# I2C-Interface.net
KiCad netlist of a schematic drawn in Altium Designer
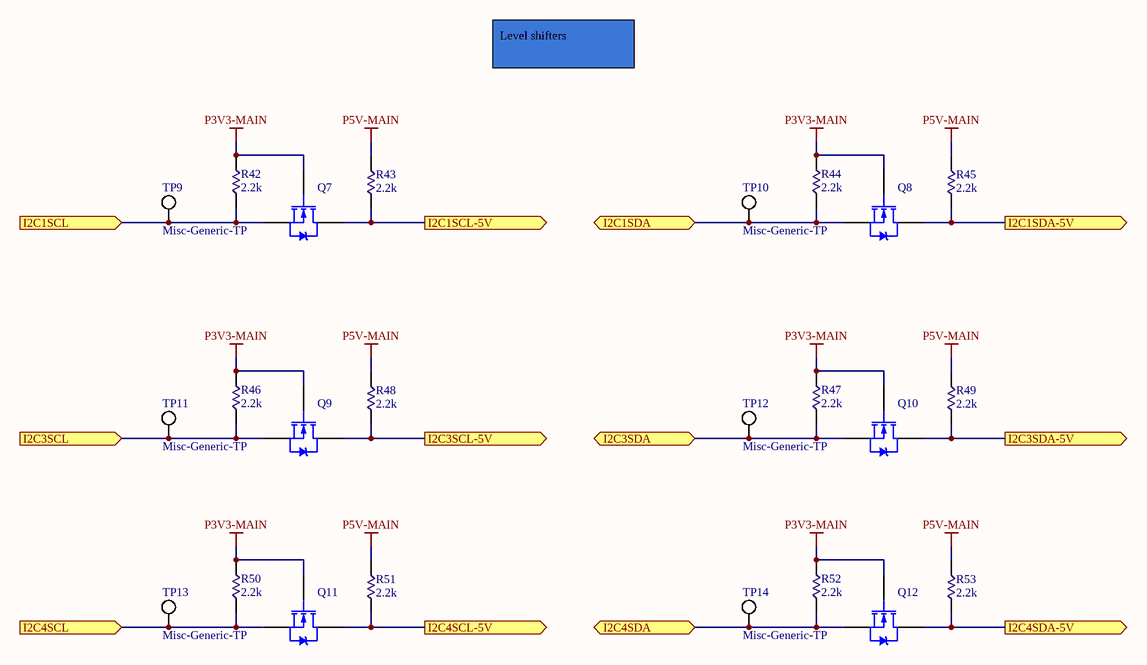
[diagram p0: I2C-Interface.SchDoc]

(export (version "E")
  (design (tool "Eeschema 10.0.6"))
  (components
    (comp (ref "Q7")
      (value "BSS138Q-7-F")
      (footprint "FOOTPRINT-DINC-SOT23-1G2S3D")
      (description "N-Channel Logic Level Enhancement Mode Field Effect Transistor")
      (fields (field (name "PUBLISHER") "Altium Limited"))
      (libsource (lib "HR-Master-Integrated") (part "Transistor-DiodesInc-BSS138-1G2S3D"))
    )
    (comp (ref "Q8")
      (value "BSS138Q-7-F")
      (footprint "FOOTPRINT-DINC-SOT23-1G2S3D")
      (description "N-Channel Logic Level Enhancement Mode Field Effect Transistor")
      (fields (field (name "PUBLISHER") "Altium Limited"))
      (libsource (lib "HR-Master-Integrated") (part "Transistor-DiodesInc-BSS138-1G2S3D"))
    )
    (comp (ref "Q9")
      (value "BSS138Q-7-F")
      (footprint "FOOTPRINT-DINC-SOT23-1G2S3D")
      (description "N-Channel Logic Level Enhancement Mode Field Effect Transistor")
      (fields (field (name "PUBLISHER") "Altium Limited"))
      (libsource (lib "HR-Master-Integrated") (part "Transistor-DiodesInc-BSS138-1G2S3D"))
    )
    (comp (ref "Q10")
      (value "BSS138Q-7-F")
      (footprint "FOOTPRINT-DINC-SOT23-1G2S3D")
      (description "N-Channel Logic Level Enhancement Mode Field Effect Transistor")
      (fields (field (name "PUBLISHER") "Altium Limited"))
      (libsource (lib "HR-Master-Integrated") (part "Transistor-DiodesInc-BSS138-1G2S3D"))
    )
    (comp (ref "Q11")
      (value "BSS138Q-7-F")
      (footprint "FOOTPRINT-DINC-SOT23-1G2S3D")
      (description "N-Channel Logic Level Enhancement Mode Field Effect Transistor")
      (fields (field (name "PUBLISHER") "Altium Limited"))
      (libsource (lib "HR-Master-Integrated") (part "Transistor-DiodesInc-BSS138-1G2S3D"))
    )
    (comp (ref "Q12")
      (value "BSS138Q-7-F")
      (footprint "FOOTPRINT-DINC-SOT23-1G2S3D")
      (description "N-Channel Logic Level Enhancement Mode Field Effect Transistor")
      (fields (field (name "PUBLISHER") "Altium Limited"))
      (libsource (lib "HR-Master-Integrated") (part "Transistor-DiodesInc-BSS138-1G2S3D"))
    )
    (comp (ref "R42")
      (value "2.2k")
      (footprint "FOOTPRINT-0805-GEN")
      (description "1/8 Watt Surface Mount Resistor")
      (fields (field (name "Comment") "SMC"))
      (libsource (lib "HR-Master-Integrated") (part "Resistor-Generic-0805-2012"))
    )
    (comp (ref "R43")
      (value "2.2k")
      (footprint "FOOTPRINT-0805-GEN")
      (description "1/8 Watt Surface Mount Resistor")
      (fields (field (name "Comment") "SMC"))
      (libsource (lib "HR-Master-Integrated") (part "Resistor-Generic-0805-2012"))
    )
    (comp (ref "R44")
      (value "2.2k")
      (footprint "FOOTPRINT-0805-GEN")
      (description "1/8 Watt Surface Mount Resistor")
      (fields (field (name "Comment") "SMC"))
      (libsource (lib "HR-Master-Integrated") (part "Resistor-Generic-0805-2012"))
    )
    (comp (ref "R45")
      (value "2.2k")
      (footprint "FOOTPRINT-0805-GEN")
      (description "1/8 Watt Surface Mount Resistor")
      (fields (field (name "Comment") "SMC"))
      (libsource (lib "HR-Master-Integrated") (part "Resistor-Generic-0805-2012"))
    )
    (comp (ref "R46")
      (value "2.2k")
      (footprint "FOOTPRINT-0805-GEN")
      (description "1/8 Watt Surface Mount Resistor")
      (fields (field (name "Comment") "SMC"))
      (libsource (lib "HR-Master-Integrated") (part "Resistor-Generic-0805-2012"))
    )
    (comp (ref "R47")
      (value "2.2k")
      (footprint "FOOTPRINT-0805-GEN")
      (description "1/8 Watt Surface Mount Resistor")
      (fields (field (name "Comment") "SMC"))
      (libsource (lib "HR-Master-Integrated") (part "Resistor-Generic-0805-2012"))
    )
    (comp (ref "R48")
      (value "2.2k")
      (footprint "FOOTPRINT-0805-GEN")
      (description "1/8 Watt Surface Mount Resistor")
      (fields (field (name "Comment") "SMC"))
      (libsource (lib "HR-Master-Integrated") (part "Resistor-Generic-0805-2012"))
    )
    (comp (ref "R49")
      (value "2.2k")
      (footprint "FOOTPRINT-0805-GEN")
      (description "1/8 Watt Surface Mount Resistor")
      (fields (field (name "Comment") "SMC"))
      (libsource (lib "HR-Master-Integrated") (part "Resistor-Generic-0805-2012"))
    )
    (comp (ref "R50")
      (value "2.2k")
      (footprint "FOOTPRINT-0805-GEN")
      (description "1/8 Watt Surface Mount Resistor")
      (fields (field (name "Comment") "SMC"))
      (libsource (lib "HR-Master-Integrated") (part "Resistor-Generic-0805-2012"))
    )
    (comp (ref "R51")
      (value "2.2k")
      (footprint "FOOTPRINT-0805-GEN")
      (description "1/8 Watt Surface Mount Resistor")
      (fields (field (name "Comment") "SMC"))
      (libsource (lib "HR-Master-Integrated") (part "Resistor-Generic-0805-2012"))
    )
    (comp (ref "R52")
      (value "2.2k")
      (footprint "FOOTPRINT-0805-GEN")
      (description "1/8 Watt Surface Mount Resistor")
      (fields (field (name "Comment") "SMC"))
      (libsource (lib "HR-Master-Integrated") (part "Resistor-Generic-0805-2012"))
    )
    (comp (ref "R53")
      (value "2.2k")
      (footprint "FOOTPRINT-0805-GEN")
      (description "1/8 Watt Surface Mount Resistor")
      (fields (field (name "Comment") "SMC"))
      (libsource (lib "HR-Master-Integrated") (part "Resistor-Generic-0805-2012"))
    )
    (comp (ref "TP9")
      (value "Misc-Generic-TP")
      (footprint "FOOTPRINT-GENERIC-TP-VIA-1MM")
      (libsource (lib "Generic") (part "Misc-Generic-TP"))
    )
    (comp (ref "TP10")
      (value "Misc-Generic-TP")
      (footprint "FOOTPRINT-GENERIC-TP-VIA-1MM")
      (libsource (lib "Generic") (part "Misc-Generic-TP"))
    )
    (comp (ref "TP11")
      (value "Misc-Generic-TP")
      (footprint "FOOTPRINT-GENERIC-TP-VIA-1MM")
      (libsource (lib "Generic") (part "Misc-Generic-TP"))
    )
    (comp (ref "TP12")
      (value "Misc-Generic-TP")
      (footprint "FOOTPRINT-GENERIC-TP-VIA-1MM")
      (libsource (lib "Generic") (part "Misc-Generic-TP"))
    )
    (comp (ref "TP13")
      (value "Misc-Generic-TP")
      (footprint "FOOTPRINT-GENERIC-TP-VIA-1MM")
      (libsource (lib "Generic") (part "Misc-Generic-TP"))
    )
    (comp (ref "TP14")
      (value "Misc-Generic-TP")
      (footprint "FOOTPRINT-GENERIC-TP-VIA-1MM")
      (libsource (lib "Generic") (part "Misc-Generic-TP"))
    )
  )
  (nets
    (net (code "1") (name "/I2C1SCL") (class "Default")
      (node (ref "Q7") (pin "2") (pinfunction "S_2") (pintype "passive"))
      (node (ref "R42") (pin "1") (pinfunction "1_1") (pintype "passive"))
      (node (ref "TP9") (pin "1") (pinfunction "TP_1") (pintype "passive"))
    )
    (net (code "2") (name "/I2C1SCL-5V") (class "Default")
      (node (ref "Q7") (pin "3") (pinfunction "D_3") (pintype "passive"))
      (node (ref "R43") (pin "2") (pinfunction "2_2") (pintype "passive"))
    )
    (net (code "3") (name "/I2C1SDA") (class "Default")
      (node (ref "Q8") (pin "2") (pinfunction "S_2") (pintype "passive"))
      (node (ref "R44") (pin "1") (pinfunction "1_1") (pintype "passive"))
      (node (ref "TP10") (pin "1") (pinfunction "TP_1") (pintype "passive"))
    )
    (net (code "4") (name "/I2C1SDA-5V") (class "Default")
      (node (ref "Q8") (pin "3") (pinfunction "D_3") (pintype "passive"))
      (node (ref "R45") (pin "2") (pinfunction "2_2") (pintype "passive"))
    )
    (net (code "5") (name "/I2C3SCL") (class "Default")
      (node (ref "Q9") (pin "2") (pinfunction "S_2") (pintype "passive"))
      (node (ref "R46") (pin "1") (pinfunction "1_1") (pintype "passive"))
      (node (ref "TP11") (pin "1") (pinfunction "TP_1") (pintype "passive"))
    )
    (net (code "6") (name "/I2C3SCL-5V") (class "Default")
      (node (ref "Q9") (pin "3") (pinfunction "D_3") (pintype "passive"))
      (node (ref "R48") (pin "2") (pinfunction "2_2") (pintype "passive"))
    )
    (net (code "7") (name "/I2C3SDA") (class "Default")
      (node (ref "Q10") (pin "2") (pinfunction "S_2") (pintype "passive"))
      (node (ref "R47") (pin "1") (pinfunction "1_1") (pintype "passive"))
      (node (ref "TP12") (pin "1") (pinfunction "TP_1") (pintype "passive"))
    )
    (net (code "8") (name "/I2C3SDA-5V") (class "Default")
      (node (ref "Q10") (pin "3") (pinfunction "D_3") (pintype "passive"))
      (node (ref "R49") (pin "2") (pinfunction "2_2") (pintype "passive"))
    )
    (net (code "9") (name "/I2C4SCL") (class "Default")
      (node (ref "Q11") (pin "2") (pinfunction "S_2") (pintype "passive"))
      (node (ref "R50") (pin "1") (pinfunction "1_1") (pintype "passive"))
      (node (ref "TP13") (pin "1") (pinfunction "TP_1") (pintype "passive"))
    )
    (net (code "10") (name "/I2C4SCL-5V") (class "Default")
      (node (ref "Q11") (pin "3") (pinfunction "D_3") (pintype "passive"))
      (node (ref "R51") (pin "2") (pinfunction "2_2") (pintype "passive"))
    )
    (net (code "11") (name "/I2C4SDA") (class "Default")
      (node (ref "Q12") (pin "2") (pinfunction "S_2") (pintype "passive"))
      (node (ref "R52") (pin "1") (pinfunction "1_1") (pintype "passive"))
      (node (ref "TP14") (pin "1") (pinfunction "TP_1") (pintype "passive"))
    )
    (net (code "12") (name "/I2C4SDA-5V") (class "Default")
      (node (ref "Q12") (pin "3") (pinfunction "D_3") (pintype "passive"))
      (node (ref "R53") (pin "2") (pinfunction "2_2") (pintype "passive"))
    )
    (net (code "13") (name "P3V3-MAIN") (class "Default")
      (node (ref "Q10") (pin "1") (pinfunction "G_1") (pintype "passive"))
      (node (ref "Q11") (pin "1") (pinfunction "G_1") (pintype "passive"))
      (node (ref "Q12") (pin "1") (pinfunction "G_1") (pintype "passive"))
      (node (ref "Q7") (pin "1") (pinfunction "G_1") (pintype "passive"))
      (node (ref "Q8") (pin "1") (pinfunction "G_1") (pintype "passive"))
      (node (ref "Q9") (pin "1") (pinfunction "G_1") (pintype "passive"))
      (node (ref "R42") (pin "2") (pinfunction "2_2") (pintype "passive"))
      (node (ref "R44") (pin "2") (pinfunction "2_2") (pintype "passive"))
      (node (ref "R46") (pin "2") (pinfunction "2_2") (pintype "passive"))
      (node (ref "R47") (pin "2") (pinfunction "2_2") (pintype "passive"))
      (node (ref "R50") (pin "2") (pinfunction "2_2") (pintype "passive"))
      (node (ref "R52") (pin "2") (pinfunction "2_2") (pintype "passive"))
    )
    (net (code "14") (name "P5V-MAIN") (class "Default")
      (node (ref "R43") (pin "1") (pinfunction "1_1") (pintype "passive"))
      (node (ref "R45") (pin "1") (pinfunction "1_1") (pintype "passive"))
      (node (ref "R48") (pin "1") (pinfunction "1_1") (pintype "passive"))
      (node (ref "R49") (pin "1") (pinfunction "1_1") (pintype "passive"))
      (node (ref "R51") (pin "1") (pinfunction "1_1") (pintype "passive"))
      (node (ref "R53") (pin "1") (pinfunction "1_1") (pintype "passive"))
    )
  )
)
